# ETH_POE_SPI_RJ45.net
KiCad netlist of a schematic drawn in Altium Designer
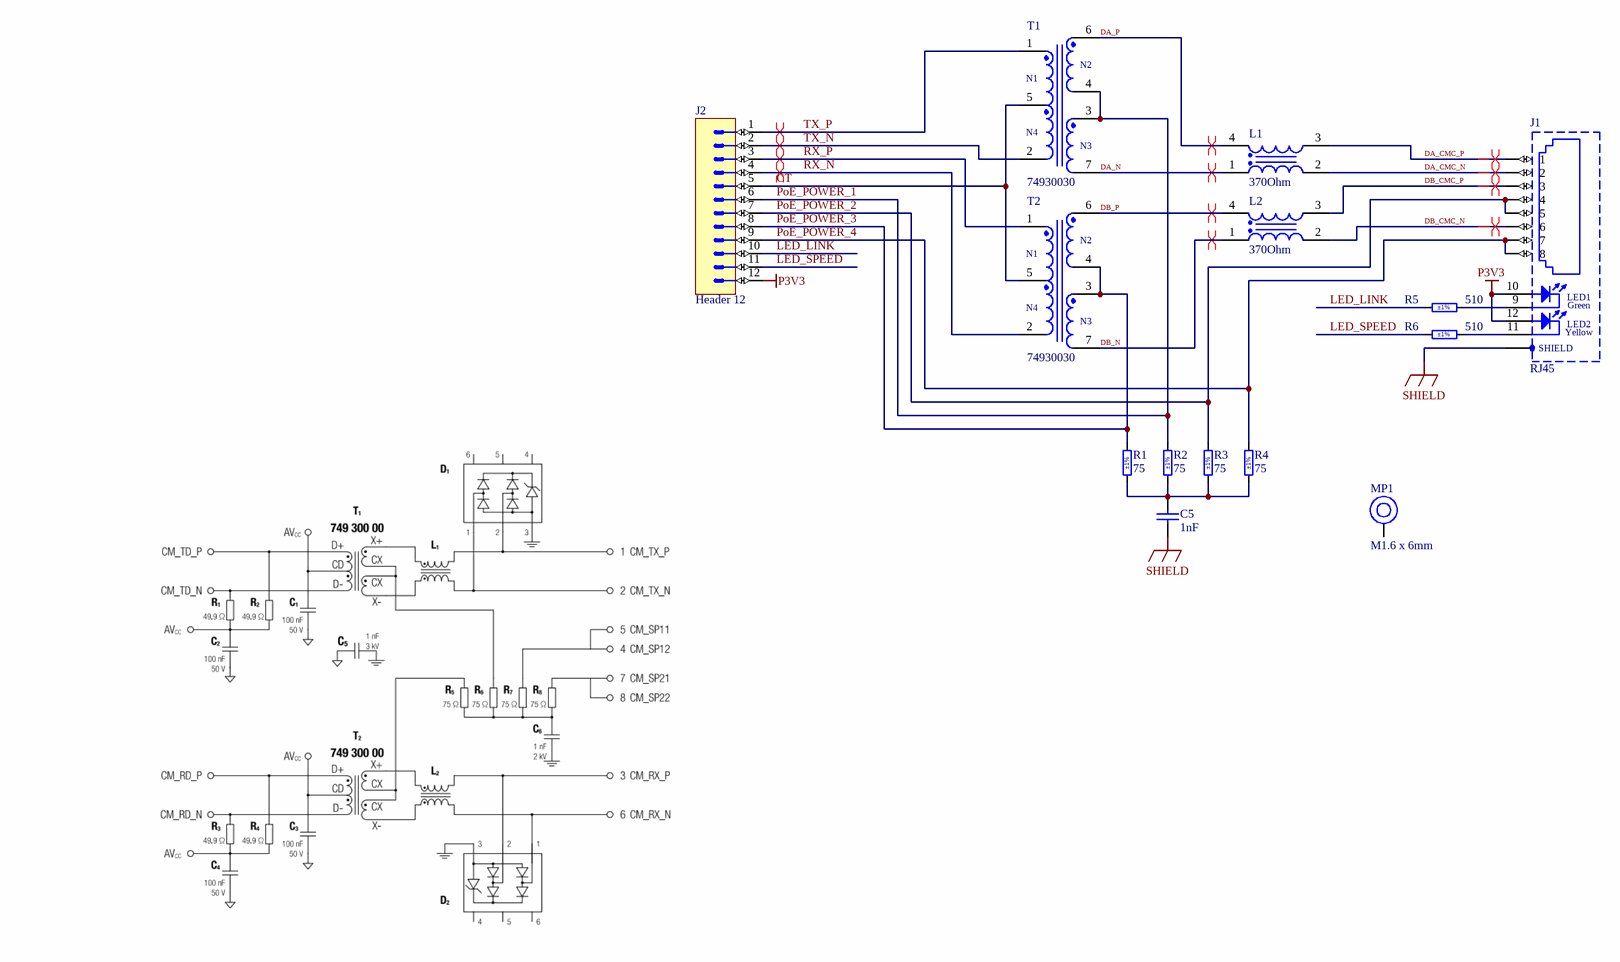
[diagram p0: ETH_POE_SPI_RJ45.SchDoc]

(export (version "E")
  (design (tool "Eeschema 10.0.6"))
  (components
    (comp (ref "C5")
      (value "1nF")
      (footprint "CAPC3216X180N")
      (description "Non-polarised capacitor")
      (fields
        (field (name "PART NUMBER") "CC1206_1NF_2KV_10%_X7R")
        (field (name "VOLTAGE") "2kV")
        (field (name "AUTHOR") "CERN DEM JLC")
      )
      (libsource (lib "Capacitors") (part "Capacitor - non polarized"))
    )
    (comp (ref "J1")
      (value "RJ45")
      (footprint "AMPHENOL_RJHSE-3381")
      (description "1 Port, 8 Positions, CAT5 RJ45 Modular Connector With Yellow And Green LEDs")
      (fields
        (field (name "PART NUMBER") "AMPHENOL_RJHSE-3381")
        (field (name "MANUFACTURER") "AMPHENOL")
        (field (name "AUTHOR") "CERN DEM JLC")
      )
      (libsource (lib "Connectors") (part "AMPHENOL_RJHSE-3381"))
    )
    (comp (ref "J2")
      (value "Header 12")
      (footprint "SAMTEC_HTSW-106-23-L-D")
      (description "Connector 12 Male")
      (fields
        (field (name "PART NUMBER") "SAMTEC_HTSW-106-23-L-D")
        (field (name "MANUFACTURER") "SAMTEC")
        (field (name "AUTHOR") "CERN DEM JLC")
      )
      (libsource (lib "Connectors") (part "Connector 12 Male"))
    )
    (comp (ref "L1")
      (value "370Ohm")
      (footprint "WE-CNSW_0805")
      (description "WE-CNSW SMT Common Mode Line Filter, size 0805, 370Ohm, 0.478uH, 50V")
      (fields
        (field (name "MANUFACTURER PART NUMBER") "744231371")
        (field (name "MANUFACTURER") "Wurth Elektronik")
      )
      (libsource (lib "WE - Passive Components") (part "WE-CNSW"))
    )
    (comp (ref "L2")
      (value "370Ohm")
      (footprint "WE-CNSW_0805")
      (description "WE-CNSW SMT Common Mode Line Filter, size 0805, 370Ohm, 0.478uH, 50V")
      (fields
        (field (name "MANUFACTURER PART NUMBER") "744231371")
        (field (name "MANUFACTURER") "Wurth Elektronik")
      )
      (libsource (lib "WE - Passive Components") (part "WE-CNSW"))
    )
    (comp (ref "MP1")
      (value "M1.6 x 6mm")
      (footprint "97730606334")
      (description "WA-SMSI SMT Steel Spacer with internal Thread, OD 3.3mm, M1.6 x 6mm")
      (fields
        (field (name "MANUFACTURER PART NUMBER") "97730606334R")
        (field (name "MANUFACTURER") "Wurth Elektronik")
      )
      (libsource (lib "WE - Electromechanical Components") (part "Spacer"))
    )
    (comp (ref "R1")
      (value "75")
      (footprint "RESC1005X40N")
      (description "Resistor - 1%")
      (fields
        (field (name "TOLERANCE") "±1%")
        (field (name "PART NUMBER") "R0402_75R_1%_0.0625W_100PPM")
        (field (name "POWER") "0.0625W")
        (field (name "AUTHOR") "CERN DEM JLC")
      )
      (libsource (lib "Resistors") (part "Resistor - 1%"))
    )
    (comp (ref "R2")
      (value "75")
      (footprint "RESC1005X40N")
      (description "Resistor - 1%")
      (fields
        (field (name "TOLERANCE") "±1%")
        (field (name "PART NUMBER") "R0402_75R_1%_0.0625W_100PPM")
        (field (name "POWER") "0.0625W")
        (field (name "AUTHOR") "CERN DEM JLC")
      )
      (libsource (lib "Resistors") (part "Resistor - 1%"))
    )
    (comp (ref "R3")
      (value "75")
      (footprint "RESC1005X40N")
      (description "Resistor - 1%")
      (fields
        (field (name "TOLERANCE") "±1%")
        (field (name "PART NUMBER") "R0402_75R_1%_0.0625W_100PPM")
        (field (name "POWER") "0.0625W")
        (field (name "AUTHOR") "CERN DEM JLC")
      )
      (libsource (lib "Resistors") (part "Resistor - 1%"))
    )
    (comp (ref "R4")
      (value "75")
      (footprint "RESC1005X40N")
      (description "Resistor - 1%")
      (fields
        (field (name "TOLERANCE") "±1%")
        (field (name "PART NUMBER") "R0402_75R_1%_0.0625W_100PPM")
        (field (name "POWER") "0.0625W")
        (field (name "AUTHOR") "CERN DEM JLC")
      )
      (libsource (lib "Resistors") (part "Resistor - 1%"))
    )
    (comp (ref "R5")
      (value "510")
      (footprint "RESC1005X40N")
      (description "Resistor - 1%")
      (fields
        (field (name "TOLERANCE") "±1%")
        (field (name "PART NUMBER") "R0402_510R_1%_0.0625W_100PPM")
        (field (name "POWER") "0.0625W")
        (field (name "AUTHOR") "CERN DEM JLC")
      )
      (libsource (lib "Resistors") (part "Resistor - 1%"))
    )
    (comp (ref "R6")
      (value "510")
      (footprint "RESC1005X40N")
      (description "Resistor - 1%")
      (fields
        (field (name "TOLERANCE") "±1%")
        (field (name "PART NUMBER") "R0402_510R_1%_0.0625W_100PPM")
        (field (name "POWER") "0.0625W")
        (field (name "AUTHOR") "CERN DEM JLC")
      )
      (libsource (lib "Resistors") (part "Resistor - 1%"))
    )
    (comp (ref "T1")
      (value "74930030")
      (footprint "74930030")
      (description "WE-STST SMT Super Tiny Signal Transformer, size 4532, 1:1, 350uH")
      (fields (field (name "MANUFACTURER") "Wurth Elektronik"))
      (libsource (lib "WE - Passive Components") (part "WE-STST"))
    )
    (comp (ref "T2")
      (value "74930030")
      (footprint "74930030")
      (description "WE-STST SMT Super Tiny Signal Transformer, size 4532, 1:1, 350uH")
      (fields (field (name "MANUFACTURER") "Wurth Elektronik"))
      (libsource (lib "WE - Passive Components") (part "WE-STST"))
    )
  )
  (nets
    (net (code "1") (name "/CT") (class "Default")
      (node (ref "J2") (pin "5") (pinfunction "5_5") (pintype "bidirectional"))
      (node (ref "T1") (pin "5") (pinfunction "5_5") (pintype "passive"))
      (node (ref "T2") (pin "5") (pinfunction "5_5") (pintype "passive"))
    )
    (net (code "2") (name "/DA_CMC_N") (class "Default")
      (node (ref "J1") (pin "2") (pinfunction "2_2") (pintype "bidirectional"))
      (node (ref "L1") (pin "2") (pinfunction "2_2") (pintype "passive"))
    )
    (net (code "3") (name "/DA_CMC_P") (class "Default")
      (node (ref "J1") (pin "1") (pinfunction "1_1") (pintype "bidirectional"))
      (node (ref "L1") (pin "3") (pinfunction "3_3") (pintype "passive"))
    )
    (net (code "4") (name "/DA_N") (class "Default")
      (node (ref "L1") (pin "1") (pinfunction "1_1") (pintype "passive"))
      (node (ref "T1") (pin "7") (pinfunction "7_7") (pintype "passive"))
    )
    (net (code "5") (name "/DA_P") (class "Default")
      (node (ref "L1") (pin "4") (pinfunction "4_4") (pintype "passive"))
      (node (ref "T1") (pin "6") (pinfunction "6_6") (pintype "passive"))
    )
    (net (code "6") (name "/DB_CMC_N") (class "Default")
      (node (ref "J1") (pin "6") (pinfunction "6_6") (pintype "bidirectional"))
      (node (ref "L2") (pin "2") (pinfunction "2_2") (pintype "passive"))
    )
    (net (code "7") (name "/DB_CMC_P") (class "Default")
      (node (ref "J1") (pin "3") (pinfunction "3_3") (pintype "bidirectional"))
      (node (ref "L2") (pin "3") (pinfunction "3_3") (pintype "passive"))
    )
    (net (code "8") (name "/DB_N") (class "Default")
      (node (ref "L2") (pin "1") (pinfunction "1_1") (pintype "passive"))
      (node (ref "T2") (pin "7") (pinfunction "7_7") (pintype "passive"))
    )
    (net (code "9") (name "/DB_P") (class "Default")
      (node (ref "L2") (pin "4") (pinfunction "4_4") (pintype "passive"))
      (node (ref "T2") (pin "6") (pinfunction "6_6") (pintype "passive"))
    )
    (net (code "10") (name "/LED_LINK") (class "Default")
      (node (ref "J2") (pin "10") (pinfunction "10_10") (pintype "bidirectional"))
      (node (ref "R5") (pin "1") (pinfunction "1_1") (pintype "passive"))
    )
    (net (code "11") (name "/LED_SPEED") (class "Default")
      (node (ref "J2") (pin "11") (pinfunction "11_11") (pintype "bidirectional"))
      (node (ref "R6") (pin "1") (pinfunction "1_1") (pintype "passive"))
    )
    (net (code "12") (name "/PoE_POWER_1") (class "Default")
      (node (ref "J2") (pin "6") (pinfunction "6_6") (pintype "bidirectional"))
      (node (ref "R2") (pin "2") (pinfunction "2_2") (pintype "passive"))
      (node (ref "T1") (pin "3") (pinfunction "3_3") (pintype "passive"))
      (node (ref "T1") (pin "4") (pinfunction "4_4") (pintype "passive"))
    )
    (net (code "13") (name "/PoE_POWER_2") (class "Default")
      (node (ref "J1") (pin "4") (pinfunction "4_4") (pintype "bidirectional"))
      (node (ref "J1") (pin "5") (pinfunction "5_5") (pintype "bidirectional"))
      (node (ref "J2") (pin "7") (pinfunction "7_7") (pintype "bidirectional"))
      (node (ref "R3") (pin "2") (pinfunction "2_2") (pintype "passive"))
    )
    (net (code "14") (name "/PoE_POWER_3") (class "Default")
      (node (ref "J2") (pin "8") (pinfunction "8_8") (pintype "bidirectional"))
      (node (ref "R1") (pin "2") (pinfunction "2_2") (pintype "passive"))
      (node (ref "T2") (pin "3") (pinfunction "3_3") (pintype "passive"))
      (node (ref "T2") (pin "4") (pinfunction "4_4") (pintype "passive"))
    )
    (net (code "15") (name "/PoE_POWER_4") (class "Default")
      (node (ref "J1") (pin "7") (pinfunction "7_7") (pintype "bidirectional"))
      (node (ref "J1") (pin "8") (pinfunction "8_8") (pintype "bidirectional"))
      (node (ref "J2") (pin "9") (pinfunction "9_9") (pintype "bidirectional"))
      (node (ref "R4") (pin "2") (pinfunction "2_2") (pintype "passive"))
    )
    (net (code "16") (name "/RX_N") (class "Default")
      (node (ref "J2") (pin "4") (pinfunction "4_4") (pintype "bidirectional"))
      (node (ref "T2") (pin "2") (pinfunction "2_2") (pintype "passive"))
    )
    (net (code "17") (name "/RX_P") (class "Default")
      (node (ref "J2") (pin "3") (pinfunction "3_3") (pintype "bidirectional"))
      (node (ref "T2") (pin "1") (pinfunction "1_1") (pintype "passive"))
    )
    (net (code "18") (name "/TX_N") (class "Default")
      (node (ref "J2") (pin "2") (pinfunction "2_2") (pintype "bidirectional"))
      (node (ref "T1") (pin "2") (pinfunction "2_2") (pintype "passive"))
    )
    (net (code "19") (name "/TX_P") (class "Default")
      (node (ref "J2") (pin "1") (pinfunction "1_1") (pintype "bidirectional"))
      (node (ref "T1") (pin "1") (pinfunction "1_1") (pintype "passive"))
    )
    (net (code "20") (name "Net-(C5-Pad2)") (class "Default")
      (node (ref "C5") (pin "2") (pinfunction "2_2") (pintype "passive"))
      (node (ref "R1") (pin "1") (pinfunction "1_1") (pintype "passive"))
      (node (ref "R2") (pin "1") (pinfunction "1_1") (pintype "passive"))
      (node (ref "R3") (pin "1") (pinfunction "1_1") (pintype "passive"))
      (node (ref "R4") (pin "1") (pinfunction "1_1") (pintype "passive"))
    )
    (net (code "21") (name "Net-(J1-ALED2)") (class "Default")
      (node (ref "J1") (pin "11") (pinfunction "ALED2_11") (pintype "passive"))
      (node (ref "R6") (pin "2") (pinfunction "2_2") (pintype "passive"))
    )
    (net (code "22") (name "Net-(J1-CLED1)") (class "Default")
      (node (ref "J1") (pin "9") (pinfunction "CLED1_9") (pintype "passive"))
      (node (ref "R5") (pin "2") (pinfunction "2_2") (pintype "passive"))
    )
    (net (code "23") (name "P3V3") (class "Default")
      (node (ref "J1") (pin "10") (pinfunction "ALED1_10") (pintype "passive"))
      (node (ref "J1") (pin "12") (pinfunction "CLED2_12") (pintype "passive"))
      (node (ref "J2") (pin "12") (pinfunction "12_12") (pintype "bidirectional"))
    )
    (net (code "24") (name "SHIELD") (class "Default")
      (node (ref "C5") (pin "1") (pinfunction "1_1") (pintype "passive"))
      (node (ref "J1") (pin "SHIELD") (pinfunction "SHIELD_SHIELD") (pintype "passive"))
    )
    (net (code "25") (name "unconnected-(MP1-Pad1)") (class "Default")
      (node (ref "MP1") (pin "1") (pinfunction "1_1") (pintype "passive"))
    )
  )
)
